# Chipset.net
KiCad netlist of a schematic drawn in Altium Designer
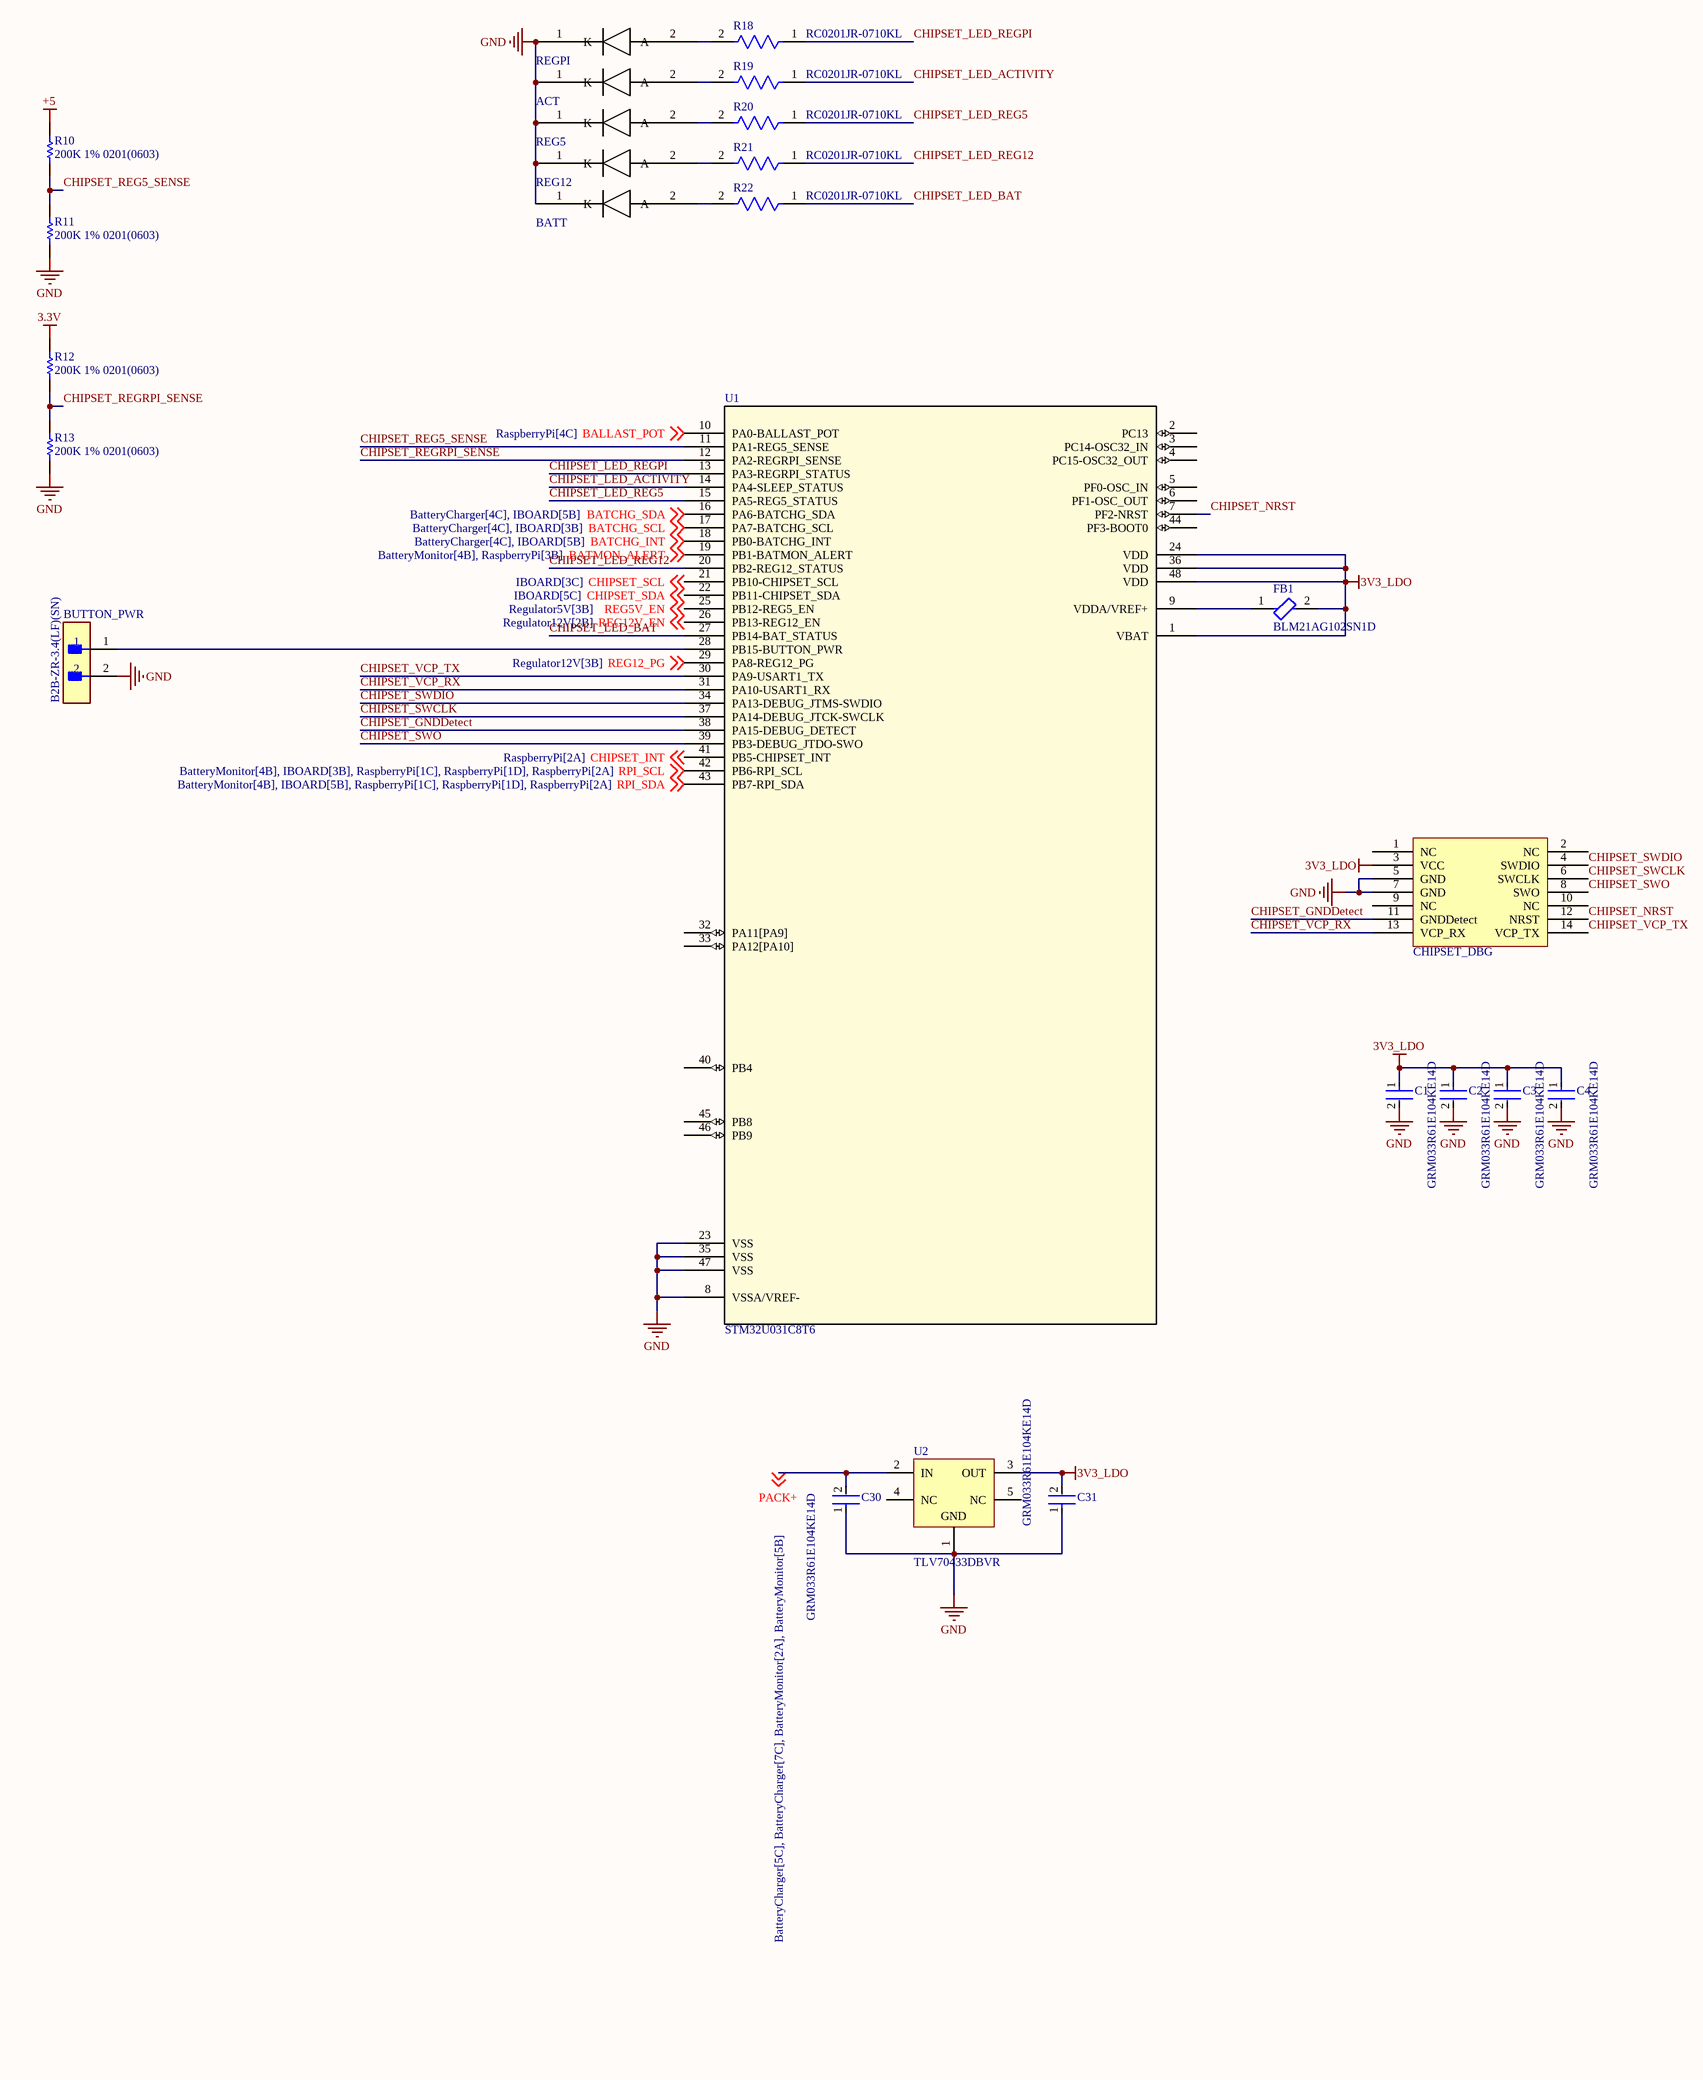
[diagram p0: Chipset.SchDoc]

(export (version "E")
  (design (tool "Eeschema 10.0.6"))
  (components
    (comp (ref "ACT")
      (value "XL-1608SURC-06")
      (footprint "XL-1608SURC-06")
      (libsource (lib "XL-1608SURC-06") (part "XL-1608SURC-06"))
    )
    (comp (ref "BATT")
      (value "XL-1608SURC-06")
      (footprint "XL-1608SURC-06")
      (libsource (lib "XL-1608SURC-06") (part "XL-1608SURC-06"))
    )
    (comp (ref "BUTTON_PWR")
      (value "B2B-ZR-3.4(LF)(SN)")
      (footprint "FP-B2B-ZR-3_4_LF_SN-MFG")
      (description "CONN HEADER VERT 2POS 1.5MM")
      (libsource (lib "Altium Content Vault") (part "3bc925449376181038e59eaffc5286c"))
    )
    (comp (ref "C1")
      (value "GRM033R61E104KE14D")
      (footprint "FP-GRM033-0_03-IPC_B")
      (description "Chip Multilayer Ceramic Capacitors for General Purpose, 0201, 0.10uF, X5R, 15%, 10%, 25V")
      (fields (field (name "TOLERANCE") "10%"))
      (libsource (lib "Altium Content Vault") (part "b4654b650e69147ec39a6b967a45e02"))
    )
    (comp (ref "C2")
      (value "GRM033R61E104KE14D")
      (footprint "FP-GRM033-0_03-IPC_B")
      (description "Chip Multilayer Ceramic Capacitors for General Purpose, 0201, 0.10uF, X5R, 15%, 10%, 25V")
      (fields (field (name "TOLERANCE") "10%"))
      (libsource (lib "Altium Content Vault") (part "b4654b650e69147ec39a6b967a45e02"))
    )
    (comp (ref "C3")
      (value "GRM033R61E104KE14D")
      (footprint "FP-GRM033-0_03-IPC_B")
      (description "Chip Multilayer Ceramic Capacitors for General Purpose, 0201, 0.10uF, X5R, 15%, 10%, 25V")
      (fields (field (name "TOLERANCE") "10%"))
      (libsource (lib "Altium Content Vault") (part "b4654b650e69147ec39a6b967a45e02"))
    )
    (comp (ref "C4")
      (value "GRM033R61E104KE14D")
      (footprint "FP-GRM033-0_03-IPC_B")
      (description "Chip Multilayer Ceramic Capacitors for General Purpose, 0201, 0.10uF, X5R, 15%, 10%, 25V")
      (fields (field (name "TOLERANCE") "10%"))
      (libsource (lib "Altium Content Vault") (part "b4654b650e69147ec39a6b967a45e02"))
    )
    (comp (ref "C30")
      (value "GRM033R61E104KE14D")
      (footprint "FP-GRM033-0_03-IPC_B")
      (description "Chip Multilayer Ceramic Capacitors for General Purpose, 0201, 0.10uF, X5R, 15%, 10%, 25V")
      (fields (field (name "TOLERANCE") "10%"))
      (libsource (lib "Altium Content Vault") (part "b4654b650e69147ec39a6b967a45e02"))
    )
    (comp (ref "C31")
      (value "GRM033R61E104KE14D")
      (footprint "FP-GRM033-0_03-IPC_B")
      (description "Chip Multilayer Ceramic Capacitors for General Purpose, 0201, 0.10uF, X5R, 15%, 10%, 25V")
      (fields (field (name "TOLERANCE") "10%"))
      (libsource (lib "Altium Content Vault") (part "b4654b650e69147ec39a6b967a45e02"))
    )
    (comp (ref "CHIPSET_DBG")
      (value "X1321WVS-2x07J-C40D53")
      (footprint "X1321WVS-2x07J-C40D53")
      (libsource (lib "X1321WVS-2x07J-C40D53") (part "X1321WVS-2x07J-C40D53"))
    )
    (comp (ref "FB1")
      (value "BLM21AG102SN1D")
      (footprint "FP-BLM21-0_2-t0_85-e0_5-MFG")
      (description "Chip Ferrite Bead, 0805, 1000Ω @ 100MHz, 0.27Ω, 25%, 600mA")
      (fields (field (name "TOLERANCE") "25%"))
      (libsource (lib "Altium Content Vault") (part "5f30dd21d616792df468990f7003faa"))
    )
    (comp (ref "R10")
      (value "200K 1% 0201(0603)")
      (footprint "RESC0201(0603)_N")
      (description "200K 0.05W 1% 0201 (0603 Metric)  SMD")
      (fields (field (name "TOLERANCE") "1 %") (field (name "POWER") "0.05 W"))
      (libsource (lib "Altium Content Vault") (part "RES"))
    )
    (comp (ref "R11")
      (value "200K 1% 0201(0603)")
      (footprint "RESC0201(0603)_N")
      (description "200K 0.05W 1% 0201 (0603 Metric)  SMD")
      (fields (field (name "TOLERANCE") "1 %") (field (name "POWER") "0.05 W"))
      (libsource (lib "Altium Content Vault") (part "RES"))
    )
    (comp (ref "R12")
      (value "200K 1% 0201(0603)")
      (footprint "RESC0201(0603)_N")
      (description "200K 0.05W 1% 0201 (0603 Metric)  SMD")
      (fields (field (name "TOLERANCE") "1 %") (field (name "POWER") "0.05 W"))
      (libsource (lib "Altium Content Vault") (part "RES"))
    )
    (comp (ref "R13")
      (value "200K 1% 0201(0603)")
      (footprint "RESC0201(0603)_N")
      (description "200K 0.05W 1% 0201 (0603 Metric)  SMD")
      (fields (field (name "TOLERANCE") "1 %") (field (name "POWER") "0.05 W"))
      (libsource (lib "Altium Content Vault") (part "RES"))
    )
    (comp (ref "R18")
      (value "RC0201JR-0710KL")
      (footprint "FP-RC0201-0_26-IPC_C")
      (description "RES SMD 10K OHM 5% 1/20W 0201")
      (fields (field (name "TOLERANCE") "5%"))
      (libsource (lib "Altium Content Vault") (part "1029c3af85768c4190bb7ad29bc67b5"))
    )
    (comp (ref "R19")
      (value "RC0201JR-0710KL")
      (footprint "FP-RC0201-0_26-IPC_C")
      (description "RES SMD 10K OHM 5% 1/20W 0201")
      (fields (field (name "TOLERANCE") "5%"))
      (libsource (lib "Altium Content Vault") (part "1029c3af85768c4190bb7ad29bc67b5"))
    )
    (comp (ref "R20")
      (value "RC0201JR-0710KL")
      (footprint "FP-RC0201-0_26-IPC_C")
      (description "RES SMD 10K OHM 5% 1/20W 0201")
      (fields (field (name "TOLERANCE") "5%"))
      (libsource (lib "Altium Content Vault") (part "1029c3af85768c4190bb7ad29bc67b5"))
    )
    (comp (ref "R21")
      (value "RC0201JR-0710KL")
      (footprint "FP-RC0201-0_26-IPC_C")
      (description "RES SMD 10K OHM 5% 1/20W 0201")
      (fields (field (name "TOLERANCE") "5%"))
      (libsource (lib "Altium Content Vault") (part "1029c3af85768c4190bb7ad29bc67b5"))
    )
    (comp (ref "R22")
      (value "RC0201JR-0710KL")
      (footprint "FP-RC0201-0_26-IPC_C")
      (description "RES SMD 10K OHM 5% 1/20W 0201")
      (fields (field (name "TOLERANCE") "5%"))
      (libsource (lib "Altium Content Vault") (part "1029c3af85768c4190bb7ad29bc67b5"))
    )
    (comp (ref "REG5")
      (value "XL-1608SURC-06")
      (footprint "XL-1608SURC-06")
      (libsource (lib "XL-1608SURC-06") (part "XL-1608SURC-06"))
    )
    (comp (ref "REG12")
      (value "XL-1608SURC-06")
      (footprint "XL-1608SURC-06")
      (libsource (lib "XL-1608SURC-06") (part "XL-1608SURC-06"))
    )
    (comp (ref "REGPI")
      (value "XL-1608SURC-06")
      (footprint "XL-1608SURC-06")
      (libsource (lib "XL-1608SURC-06") (part "XL-1608SURC-06"))
    )
    (comp (ref "U1")
      (value "STM32U031C8T6")
      (footprint "LQFP48_STM")
      (description "No Description Available")
      (libsource (lib "STM32U031C8T6") (part "STM32U031C8T6"))
    )
    (comp (ref "U2")
      (value "TLV70433DBVR")
      (footprint "DBV0005A_M")
      (fields (field (name "MANUFACTURER") "Texas Instruments"))
      (libsource (lib "Altium Content Vault") (part "TI-TLV704XXDBV5"))
    )
  )
  (nets
    (net (code "1") (name "+5") (class "Default")
      (node (ref "R10") (pin "2") (pinfunction "2_2") (pintype "passive"))
    )
    (net (code "2") (name "/CHIPSET_GNDDetect") (class "Default")
      (node (ref "CHIPSET_DBG") (pin "11") (pinfunction "GNDDetect_11") (pintype "passive"))
      (node (ref "U1") (pin "38") (pinfunction "PA15-DEBUG_DETECT_38") (pintype "passive"))
    )
    (net (code "3") (name "/CHIPSET_LED_ACTIVITY") (class "Default")
      (node (ref "R19") (pin "1") (pinfunction "1_1") (pintype "passive"))
      (node (ref "U1") (pin "14") (pinfunction "PA4-SLEEP_STATUS_14") (pintype "passive"))
    )
    (net (code "4") (name "/CHIPSET_LED_BAT") (class "Default")
      (node (ref "R22") (pin "1") (pinfunction "1_1") (pintype "passive"))
      (node (ref "U1") (pin "27") (pinfunction "PB14-BAT_STATUS_27") (pintype "passive"))
    )
    (net (code "5") (name "/CHIPSET_LED_REG5") (class "Default")
      (node (ref "R20") (pin "1") (pinfunction "1_1") (pintype "passive"))
      (node (ref "U1") (pin "15") (pinfunction "PA5-REG5_STATUS_15") (pintype "passive"))
    )
    (net (code "6") (name "/CHIPSET_LED_REG12") (class "Default")
      (node (ref "R21") (pin "1") (pinfunction "1_1") (pintype "passive"))
      (node (ref "U1") (pin "20") (pinfunction "PB2-REG12_STATUS_20") (pintype "passive"))
    )
    (net (code "7") (name "/CHIPSET_LED_REGPI") (class "Default")
      (node (ref "R18") (pin "1") (pinfunction "1_1") (pintype "passive"))
      (node (ref "U1") (pin "13") (pinfunction "PA3-REGRPI_STATUS_13") (pintype "passive"))
    )
    (net (code "8") (name "/CHIPSET_NRST") (class "Default")
      (node (ref "CHIPSET_DBG") (pin "12") (pinfunction "NRST_12") (pintype "passive"))
      (node (ref "U1") (pin "7") (pinfunction "PF2-NRST_7") (pintype "bidirectional"))
    )
    (net (code "9") (name "/CHIPSET_REG5_SENSE") (class "Default")
      (node (ref "R10") (pin "1") (pinfunction "1_1") (pintype "passive"))
      (node (ref "R11") (pin "2") (pinfunction "2_2") (pintype "passive"))
      (node (ref "U1") (pin "11") (pinfunction "PA1-REG5_SENSE_11") (pintype "passive"))
    )
    (net (code "10") (name "/CHIPSET_REGRPI_SENSE") (class "Default")
      (node (ref "R12") (pin "1") (pinfunction "1_1") (pintype "passive"))
      (node (ref "R13") (pin "2") (pinfunction "2_2") (pintype "passive"))
      (node (ref "U1") (pin "12") (pinfunction "PA2-REGRPI_SENSE_12") (pintype "passive"))
    )
    (net (code "11") (name "/CHIPSET_SWCLK") (class "Default")
      (node (ref "CHIPSET_DBG") (pin "6") (pinfunction "SWCLK_6") (pintype "passive"))
      (node (ref "U1") (pin "37") (pinfunction "PA14-DEBUG_JTCK-SWCLK_37") (pintype "passive"))
    )
    (net (code "12") (name "/CHIPSET_SWDIO") (class "Default")
      (node (ref "CHIPSET_DBG") (pin "4") (pinfunction "SWDIO_4") (pintype "passive"))
      (node (ref "U1") (pin "34") (pinfunction "PA13-DEBUG_JTMS-SWDIO_34") (pintype "passive"))
    )
    (net (code "13") (name "/CHIPSET_SWO") (class "Default")
      (node (ref "CHIPSET_DBG") (pin "8") (pinfunction "SWO_8") (pintype "passive"))
      (node (ref "U1") (pin "39") (pinfunction "PB3-DEBUG_JTDO-SWO_39") (pintype "passive"))
    )
    (net (code "14") (name "/CHIPSET_VCP_RX") (class "Default")
      (node (ref "CHIPSET_DBG") (pin "13") (pinfunction "VCP_RX_13") (pintype "passive"))
      (node (ref "U1") (pin "31") (pinfunction "PA10-USART1_RX_31") (pintype "passive"))
    )
    (net (code "15") (name "/CHIPSET_VCP_TX") (class "Default")
      (node (ref "CHIPSET_DBG") (pin "14") (pinfunction "VCP_TX_14") (pintype "passive"))
      (node (ref "U1") (pin "30") (pinfunction "PA9-USART1_TX_30") (pintype "passive"))
    )
    (net (code "16") (name "3.3V") (class "Default")
      (node (ref "R12") (pin "2") (pinfunction "2_2") (pintype "passive"))
    )
    (net (code "17") (name "3V3_LDO") (class "Default")
      (node (ref "C1") (pin "1") (pinfunction "1_1") (pintype "passive"))
      (node (ref "C2") (pin "1") (pinfunction "1_1") (pintype "passive"))
      (node (ref "C3") (pin "1") (pinfunction "1_1") (pintype "passive"))
      (node (ref "C31") (pin "2") (pinfunction "2_2") (pintype "passive"))
      (node (ref "C4") (pin "1") (pinfunction "1_1") (pintype "passive"))
      (node (ref "CHIPSET_DBG") (pin "3") (pinfunction "VCC_3") (pintype "passive"))
      (node (ref "FB1") (pin "2") (pinfunction "2_2") (pintype "passive"))
      (node (ref "U1") (pin "1") (pinfunction "VBAT_1") (pintype "power_in"))
      (node (ref "U1") (pin "24") (pinfunction "VDD_24") (pintype "power_in"))
      (node (ref "U1") (pin "36") (pinfunction "VDD_36") (pintype "power_in"))
      (node (ref "U1") (pin "48") (pinfunction "VDD_48") (pintype "power_in"))
      (node (ref "U2") (pin "3") (pinfunction "OUT_3") (pintype "power_in"))
    )
    (net (code "18") (name "BALLAST_POT") (class "Default")
      (node (ref "U1") (pin "10") (pinfunction "PA0-BALLAST_POT_10") (pintype "passive"))
    )
    (net (code "19") (name "BATCHG_INT") (class "Default")
      (node (ref "U1") (pin "18") (pinfunction "PB0-BATCHG_INT_18") (pintype "passive"))
    )
    (net (code "20") (name "BATCHG_SCL") (class "Default")
      (node (ref "U1") (pin "17") (pinfunction "PA7-BATCHG_SCL_17") (pintype "passive"))
    )
    (net (code "21") (name "BATCHG_SDA") (class "Default")
      (node (ref "U1") (pin "16") (pinfunction "PA6-BATCHG_SDA_16") (pintype "passive"))
    )
    (net (code "22") (name "BATMON_ALERT") (class "Default")
      (node (ref "U1") (pin "19") (pinfunction "PB1-BATMON_ALERT_19") (pintype "passive"))
    )
    (net (code "23") (name "CHIPSET_INT") (class "Default")
      (node (ref "U1") (pin "41") (pinfunction "PB5-CHIPSET_INT_41") (pintype "passive"))
    )
    (net (code "24") (name "CHIPSET_SCL") (class "Default")
      (node (ref "U1") (pin "21") (pinfunction "PB10-CHIPSET_SCL_21") (pintype "passive"))
    )
    (net (code "25") (name "CHIPSET_SDA") (class "Default")
      (node (ref "U1") (pin "22") (pinfunction "PB11-CHIPSET_SDA_22") (pintype "passive"))
    )
    (net (code "26") (name "GND") (class "Default")
      (node (ref "ACT") (pin "1") (pinfunction "K_1") (pintype "power_in"))
      (node (ref "BATT") (pin "1") (pinfunction "K_1") (pintype "power_in"))
      (node (ref "BUTTON_PWR") (pin "2") (pinfunction "2_2") (pintype "passive"))
      (node (ref "C1") (pin "2") (pinfunction "2_2") (pintype "passive"))
      (node (ref "C2") (pin "2") (pinfunction "2_2") (pintype "passive"))
      (node (ref "C3") (pin "2") (pinfunction "2_2") (pintype "passive"))
      (node (ref "C30") (pin "1") (pinfunction "1_1") (pintype "passive"))
      (node (ref "C31") (pin "1") (pinfunction "1_1") (pintype "passive"))
      (node (ref "C4") (pin "2") (pinfunction "2_2") (pintype "passive"))
      (node (ref "CHIPSET_DBG") (pin "5") (pinfunction "GND_5") (pintype "passive"))
      (node (ref "CHIPSET_DBG") (pin "7") (pinfunction "GND_7") (pintype "passive"))
      (node (ref "R11") (pin "1") (pinfunction "1_1") (pintype "passive"))
      (node (ref "R13") (pin "1") (pinfunction "1_1") (pintype "passive"))
      (node (ref "REG12") (pin "1") (pinfunction "K_1") (pintype "power_in"))
      (node (ref "REG5") (pin "1") (pinfunction "K_1") (pintype "power_in"))
      (node (ref "REGPI") (pin "1") (pinfunction "K_1") (pintype "power_in"))
      (node (ref "U1") (pin "23") (pinfunction "VSS_23") (pintype "power_in"))
      (node (ref "U1") (pin "35") (pinfunction "VSS_35") (pintype "power_in"))
      (node (ref "U1") (pin "47") (pinfunction "VSS_47") (pintype "power_in"))
      (node (ref "U1") (pin "8") (pinfunction "VSSA/VREF-_8") (pintype "power_in"))
      (node (ref "U2") (pin "1") (pinfunction "GND_1") (pintype "power_in"))
    )
    (net (code "27") (name "Net-(ACT-A)") (class "Default")
      (node (ref "ACT") (pin "2") (pinfunction "A_2") (pintype "power_in"))
      (node (ref "R19") (pin "2") (pinfunction "2_2") (pintype "passive"))
    )
    (net (code "28") (name "Net-(BATT-A)") (class "Default")
      (node (ref "BATT") (pin "2") (pinfunction "A_2") (pintype "power_in"))
      (node (ref "R22") (pin "2") (pinfunction "2_2") (pintype "passive"))
    )
    (net (code "29") (name "Net-(REG5-A)") (class "Default")
      (node (ref "R20") (pin "2") (pinfunction "2_2") (pintype "passive"))
      (node (ref "REG5") (pin "2") (pinfunction "A_2") (pintype "power_in"))
    )
    (net (code "30") (name "Net-(REG12-A)") (class "Default")
      (node (ref "R21") (pin "2") (pinfunction "2_2") (pintype "passive"))
      (node (ref "REG12") (pin "2") (pinfunction "A_2") (pintype "power_in"))
    )
    (net (code "31") (name "Net-(REGPI-A)") (class "Default")
      (node (ref "R18") (pin "2") (pinfunction "2_2") (pintype "passive"))
      (node (ref "REGPI") (pin "2") (pinfunction "A_2") (pintype "power_in"))
    )
    (net (code "32") (name "Net-(U1-PB15-BUTTON_PWR)") (class "Default")
      (node (ref "BUTTON_PWR") (pin "1") (pinfunction "1_1") (pintype "passive"))
      (node (ref "U1") (pin "28") (pinfunction "PB15-BUTTON_PWR_28") (pintype "passive"))
    )
    (net (code "33") (name "Net-(U1-VDDA{slash}VREF+)") (class "Default")
      (node (ref "FB1") (pin "1") (pinfunction "1_1") (pintype "passive"))
      (node (ref "U1") (pin "9") (pinfunction "VDDA/VREF+_9") (pintype "power_in"))
    )
    (net (code "34") (name "PACK+") (class "Default")
      (node (ref "C30") (pin "2") (pinfunction "2_2") (pintype "passive"))
      (node (ref "U2") (pin "2") (pinfunction "IN_2") (pintype "power_in"))
    )
    (net (code "35") (name "REG5V_EN") (class "Default")
      (node (ref "U1") (pin "25") (pinfunction "PB12-REG5_EN_25") (pintype "passive"))
    )
    (net (code "36") (name "REG12V_EN") (class "Default")
      (node (ref "U1") (pin "26") (pinfunction "PB13-REG12_EN_26") (pintype "passive"))
    )
    (net (code "37") (name "REG12_PG") (class "Default")
      (node (ref "U1") (pin "29") (pinfunction "PA8-REG12_PG_29") (pintype "passive"))
    )
    (net (code "38") (name "RPI_SCL") (class "Default")
      (node (ref "U1") (pin "42") (pinfunction "PB6-RPI_SCL_42") (pintype "passive"))
    )
    (net (code "39") (name "RPI_SDA") (class "Default")
      (node (ref "U1") (pin "43") (pinfunction "PB7-RPI_SDA_43") (pintype "passive"))
    )
    (net (code "40") (name "unconnected-(CHIPSET_DBG-NC-Pad1)") (class "Default")
      (node (ref "CHIPSET_DBG") (pin "1") (pinfunction "NC_1") (pintype "passive"))
    )
    (net (code "41") (name "unconnected-(CHIPSET_DBG-NC-Pad2)") (class "Default")
      (node (ref "CHIPSET_DBG") (pin "2") (pinfunction "NC_2") (pintype "passive"))
    )
    (net (code "42") (name "unconnected-(CHIPSET_DBG-NC-Pad9)") (class "Default")
      (node (ref "CHIPSET_DBG") (pin "9") (pinfunction "NC_9") (pintype "passive"))
    )
    (net (code "43") (name "unconnected-(CHIPSET_DBG-NC-Pad10)") (class "Default")
      (node (ref "CHIPSET_DBG") (pin "10") (pinfunction "NC_10") (pintype "passive"))
    )
    (net (code "44") (name "unconnected-(U1-PA11[PA9]-Pad32)") (class "Default")
      (node (ref "U1") (pin "32") (pinfunction "PA11[PA9]_32") (pintype "bidirectional"))
    )
    (net (code "45") (name "unconnected-(U1-PA12[PA10]-Pad33)") (class "Default")
      (node (ref "U1") (pin "33") (pinfunction "PA12[PA10]_33") (pintype "bidirectional"))
    )
    (net (code "46") (name "unconnected-(U1-PB4-Pad40)") (class "Default")
      (node (ref "U1") (pin "40") (pinfunction "PB4_40") (pintype "bidirectional"))
    )
    (net (code "47") (name "unconnected-(U1-PB8-Pad45)") (class "Default")
      (node (ref "U1") (pin "45") (pinfunction "PB8_45") (pintype "bidirectional"))
    )
    (net (code "48") (name "unconnected-(U1-PB9-Pad46)") (class "Default")
      (node (ref "U1") (pin "46") (pinfunction "PB9_46") (pintype "bidirectional"))
    )
    (net (code "49") (name "unconnected-(U1-PC13-Pad2)") (class "Default")
      (node (ref "U1") (pin "2") (pinfunction "PC13_2") (pintype "bidirectional"))
    )
    (net (code "50") (name "unconnected-(U1-PC14-OSC32_IN-Pad3)") (class "Default")
      (node (ref "U1") (pin "3") (pinfunction "PC14-OSC32_IN_3") (pintype "bidirectional"))
    )
    (net (code "51") (name "unconnected-(U1-PC15-OSC32_OUT-Pad4)") (class "Default")
      (node (ref "U1") (pin "4") (pinfunction "PC15-OSC32_OUT_4") (pintype "bidirectional"))
    )
    (net (code "52") (name "unconnected-(U1-PF0-OSC_IN-Pad5)") (class "Default")
      (node (ref "U1") (pin "5") (pinfunction "PF0-OSC_IN_5") (pintype "bidirectional"))
    )
    (net (code "53") (name "unconnected-(U1-PF1-OSC_OUT-Pad6)") (class "Default")
      (node (ref "U1") (pin "6") (pinfunction "PF1-OSC_OUT_6") (pintype "bidirectional"))
    )
    (net (code "54") (name "unconnected-(U1-PF3-BOOT0-Pad44)") (class "Default")
      (node (ref "U1") (pin "44") (pinfunction "PF3-BOOT0_44") (pintype "bidirectional"))
    )
    (net (code "55") (name "unconnected-(U2-NC-Pad4)") (class "Default")
      (node (ref "U2") (pin "4") (pinfunction "NC_4") (pintype "passive"))
    )
    (net (code "56") (name "unconnected-(U2-NC-Pad5)") (class "Default")
      (node (ref "U2") (pin "5") (pinfunction "NC_5") (pintype "passive"))
    )
  )
)
